# rtc.net
KiCad netlist of a schematic drawn in Altium Designer
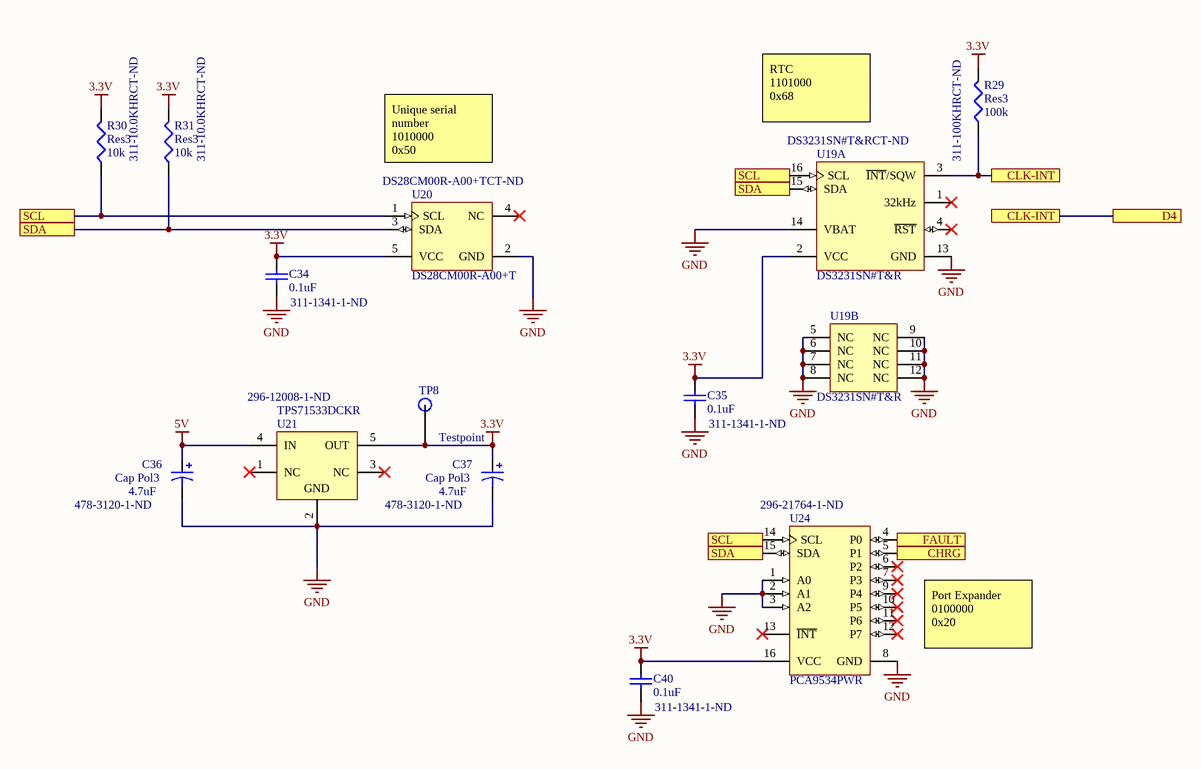
[diagram p0: rtc.SchDoc]

(export (version "E")
  (design (tool "Eeschema 10.0.6"))
  (components
    (comp (ref "C34")
      (value "0.1uF")
      (footprint "1608[0603]")
      (description "Capacitor (Semiconductor SIM Model)")
      (fields
        (field (name "SUPPLIER PART NUMBER 1") "311-1341-1-ND")
        (field (name "MANUFACTURER") "Yageo")
        (field (name "MANUFACTURER PART NUMBER") "CC0603KRX7R8BB104")
      )
      (libsource (lib "Miscellaneous Devices") (part "Cap Semi"))
    )
    (comp (ref "C35")
      (value "0.1uF")
      (footprint "1608[0603]")
      (description "Capacitor (Semiconductor SIM Model)")
      (fields
        (field (name "SUPPLIER PART NUMBER 1") "311-1341-1-ND")
        (field (name "MANUFACTURER") "Yageo")
        (field (name "MANUFACTURER PART NUMBER") "CC0603KRX7R8BB104")
      )
      (libsource (lib "Miscellaneous Devices") (part "Cap Semi"))
    )
    (comp (ref "C36")
      (value "Cap Pol3")
      (footprint "1206-pol")
      (description "Polarized Capacitor (Surface Mount)")
      (fields
        (field (name "ALTIUM_VALUE") "4.7uF")
        (field (name "SUPPLIER PART NUMBER 1") "478-3120-1-ND")
        (field (name "MANUFACTURER") "AVX Corporation")
        (field (name "MANUFACTURER PART NUMBER") "NOJA475M010RWJ")
      )
      (libsource (lib "Miscellaneous Devices") (part "Cap Pol3"))
    )
    (comp (ref "C37")
      (value "Cap Pol3")
      (footprint "1206-pol")
      (description "Polarized Capacitor (Surface Mount)")
      (fields
        (field (name "ALTIUM_VALUE") "4.7uF")
        (field (name "SUPPLIER PART NUMBER 1") "478-3120-1-ND")
        (field (name "MANUFACTURER") "AVX Corporation")
        (field (name "MANUFACTURER PART NUMBER") "NOJA475M010RWJ")
      )
      (libsource (lib "Miscellaneous Devices") (part "Cap Pol3"))
    )
    (comp (ref "C40")
      (value "0.1uF")
      (footprint "1608[0603]")
      (description "Capacitor (Semiconductor SIM Model)")
      (fields
        (field (name "SUPPLIER PART NUMBER 1") "311-1341-1-ND")
        (field (name "MANUFACTURER") "Yageo")
        (field (name "MANUFACTURER PART NUMBER") "CC0603KRX7R8BB104")
      )
      (libsource (lib "Miscellaneous Devices") (part "Cap Semi"))
    )
    (comp (ref "R29")
      (value "Res3")
      (footprint "J1-0603")
      (description "Resistor")
      (fields
        (field (name "ALTIUM_VALUE") "100k")
        (field (name "SUPPLIER PART NUMBER 1") "311-100KHRCT-ND")
        (field (name "MANUFACTURER") "Yageo")
        (field (name "MANUFACTURER PART NUMBER") "RC0603FR-07100KL")
        (field (name "PUBLISHER") "Altium Limited")
      )
      (libsource (lib "Miscellaneous Devices") (part "Res3"))
    )
    (comp (ref "R30")
      (value "Res3")
      (footprint "J1-0603")
      (description "Resistor")
      (fields
        (field (name "ALTIUM_VALUE") "10k")
        (field (name "SUPPLIER PART NUMBER 1") "311-10.0KHRCT-ND")
        (field (name "MANUFACTURER") "Yageo")
        (field (name "MANUFACTURER PART NUMBER") "RC0603FR-0710KL")
        (field (name "PUBLISHER") "Altium Limited")
      )
      (libsource (lib "Miscellaneous Devices") (part "Res3"))
    )
    (comp (ref "R31")
      (value "Res3")
      (footprint "J1-0603")
      (description "Resistor")
      (fields
        (field (name "ALTIUM_VALUE") "10k")
        (field (name "SUPPLIER PART NUMBER 1") "311-10.0KHRCT-ND")
        (field (name "MANUFACTURER") "Yageo")
        (field (name "MANUFACTURER PART NUMBER") "RC0603FR-0710KL")
        (field (name "PUBLISHER") "Altium Limited")
      )
      (libsource (lib "Miscellaneous Devices") (part "Res3"))
    )
    (comp (ref "TP8")
      (value "Testpoint")
      (footprint "testpoint")
      (description "SMT Testpoint")
      (libsource (lib "testpoints") (part "SMT Testpoint"))
    )
    (comp (ref "U19")
      (value "DS3231SN#T&R")
      (footprint "W16#H2_M")
      (fields
        (field (name "SUPPLIER PART NUMBER 1") "DS3231SN#T&RCT-ND")
        (field (name "MANUFACTURER") "Maxim")
      )
      (libsource (lib "Altium Content Vault") (part "MAX-RTC-16-DS3231S-W16#H2"))
    )
    (comp (ref "U20")
      (value "DS28CM00R-A00+T")
      (footprint "U5+1_M")
      (description "I²C/SMBus Silicon Serial Number, 5-pin SOT23, -40° to + 85° C, Pb-Free, Tape and Reel")
      (fields
        (field (name "SUPPLIER PART NUMBER 1") "DS28CM00R-A00+TCT-ND")
        (field (name "MANUFACTURER") "Maxim")
      )
      (libsource (lib "Altium Content Vault") (part "PR-MCTL-DS28CM00-SOT5"))
    )
    (comp (ref "U21")
      (value "TPS71533DCKR")
      (footprint "DCK0005A_L")
      (fields
        (field (name "MANUFACTURER") "Texas Instruments")
        (field (name "SUPPLIER PART NUMBER 1") "296-12008-1-ND")
      )
      (libsource (lib "Altium Content Vault") (part "TI-TPS71XXXX-XXDCK5"))
    )
    (comp (ref "U24")
      (value "PCA9534PWR")
      (footprint "PW0016A_N")
      (fields
        (field (name "MANUFACTURER") "Texas Instruments")
        (field (name "SUPPLIER PART NUMBER 1") "296-21764-1-ND")
      )
      (libsource (lib "Altium Content Vault") (part "TI-PCA9534-TSSOP_PW-16"))
    )
  )
  (nets
    (net (code "1") (name "/CHRG") (class "Default")
      (node (ref "U24") (pin "5") (pinfunction "P1_5") (pintype "bidirectional"))
    )
    (net (code "2") (name "/CLK-INT") (class "Default")
      (node (ref "R29") (pin "1") (pinfunction "1_1") (pintype "passive"))
      (node (ref "U19") (pin "3") (pinfunction "~{INT}/SQW_3") (pintype "open_collector"))
    )
    (net (code "3") (name "/FAULT") (class "Default")
      (node (ref "U24") (pin "4") (pinfunction "P0_4") (pintype "bidirectional"))
    )
    (net (code "4") (name "/SCL") (class "Default")
      (node (ref "R30") (pin "1") (pinfunction "1_1") (pintype "passive"))
      (node (ref "U19") (pin "16") (pinfunction "SCL_16") (pintype "input"))
      (node (ref "U20") (pin "1") (pinfunction "SCL_1") (pintype "input"))
      (node (ref "U24") (pin "14") (pinfunction "SCL_14") (pintype "input"))
    )
    (net (code "5") (name "/SDA") (class "Default")
      (node (ref "R31") (pin "1") (pinfunction "1_1") (pintype "passive"))
      (node (ref "U19") (pin "15") (pinfunction "SDA_15") (pintype "bidirectional"))
      (node (ref "U20") (pin "3") (pinfunction "SDA_3") (pintype "bidirectional"))
      (node (ref "U24") (pin "15") (pinfunction "SDA_15") (pintype "bidirectional"))
    )
    (net (code "6") (name "3.3V") (class "Default")
      (node (ref "C34") (pin "1") (pinfunction "1_1") (pintype "passive"))
      (node (ref "C35") (pin "1") (pinfunction "1_1") (pintype "passive"))
      (node (ref "C37") (pin "1") (pinfunction "1_1") (pintype "passive"))
      (node (ref "C40") (pin "1") (pinfunction "1_1") (pintype "passive"))
      (node (ref "R29") (pin "2") (pinfunction "2_2") (pintype "passive"))
      (node (ref "R30") (pin "2") (pinfunction "2_2") (pintype "passive"))
      (node (ref "R31") (pin "2") (pinfunction "2_2") (pintype "passive"))
      (node (ref "TP8") (pin "1") (pinfunction "1_1") (pintype "passive"))
      (node (ref "U19") (pin "2") (pinfunction "VCC_2") (pintype "power_in"))
      (node (ref "U20") (pin "5") (pinfunction "VCC_5") (pintype "power_in"))
      (node (ref "U21") (pin "5") (pinfunction "OUT_5") (pintype "power_in"))
      (node (ref "U24") (pin "16") (pinfunction "VCC_16") (pintype "power_in"))
    )
    (net (code "7") (name "5V") (class "Default")
      (node (ref "C36") (pin "1") (pinfunction "1_1") (pintype "passive"))
      (node (ref "U21") (pin "4") (pinfunction "IN_4") (pintype "power_in"))
    )
    (net (code "8") (name "GND") (class "Default")
      (node (ref "C34") (pin "2") (pinfunction "2_2") (pintype "passive"))
      (node (ref "C35") (pin "2") (pinfunction "2_2") (pintype "passive"))
      (node (ref "C36") (pin "2") (pinfunction "2_2") (pintype "passive"))
      (node (ref "C37") (pin "2") (pinfunction "2_2") (pintype "passive"))
      (node (ref "C40") (pin "2") (pinfunction "2_2") (pintype "passive"))
      (node (ref "U19") (pin "10") (pinfunction "NC_10") (pintype "passive"))
      (node (ref "U19") (pin "11") (pinfunction "NC_11") (pintype "passive"))
      (node (ref "U19") (pin "12") (pinfunction "NC_12") (pintype "passive"))
      (node (ref "U19") (pin "13") (pinfunction "GND_13") (pintype "power_in"))
      (node (ref "U19") (pin "14") (pinfunction "VBAT_14") (pintype "power_in"))
      (node (ref "U19") (pin "5") (pinfunction "NC_5") (pintype "passive"))
      (node (ref "U19") (pin "6") (pinfunction "NC_6") (pintype "passive"))
      (node (ref "U19") (pin "7") (pinfunction "NC_7") (pintype "passive"))
      (node (ref "U19") (pin "8") (pinfunction "NC_8") (pintype "passive"))
      (node (ref "U19") (pin "9") (pinfunction "NC_9") (pintype "passive"))
      (node (ref "U20") (pin "2") (pinfunction "GND_2") (pintype "power_in"))
      (node (ref "U21") (pin "2") (pinfunction "GND_2") (pintype "power_in"))
      (node (ref "U24") (pin "1") (pinfunction "A0_1") (pintype "input"))
      (node (ref "U24") (pin "2") (pinfunction "A1_2") (pintype "input"))
      (node (ref "U24") (pin "3") (pinfunction "A2_3") (pintype "input"))
      (node (ref "U24") (pin "8") (pinfunction "GND_8") (pintype "power_in"))
    )
    (net (code "9") (name "unconnected-(U19A-32kHz-Pad1)") (class "Default")
      (node (ref "U19") (pin "1") (pinfunction "32kHz_1") (pintype "open_collector+no_connect"))
    )
    (net (code "10") (name "unconnected-(U19A-~{RST}-Pad4)") (class "Default")
      (node (ref "U19") (pin "4") (pinfunction "~{RST}_4") (pintype "bidirectional+no_connect"))
    )
    (net (code "11") (name "unconnected-(U20-NC-Pad4)") (class "Default")
      (node (ref "U20") (pin "4") (pinfunction "NC_4") (pintype "passive+no_connect"))
    )
    (net (code "12") (name "unconnected-(U21-NC-Pad1)") (class "Default")
      (node (ref "U21") (pin "1") (pinfunction "NC_1") (pintype "passive+no_connect"))
    )
    (net (code "13") (name "unconnected-(U21-NC-Pad3)") (class "Default")
      (node (ref "U21") (pin "3") (pinfunction "NC_3") (pintype "passive+no_connect"))
    )
    (net (code "14") (name "unconnected-(U24-P2-Pad6)") (class "Default")
      (node (ref "U24") (pin "6") (pinfunction "P2_6") (pintype "bidirectional+no_connect"))
    )
    (net (code "15") (name "unconnected-(U24-P3-Pad7)") (class "Default")
      (node (ref "U24") (pin "7") (pinfunction "P3_7") (pintype "bidirectional+no_connect"))
    )
    (net (code "16") (name "unconnected-(U24-P4-Pad9)") (class "Default")
      (node (ref "U24") (pin "9") (pinfunction "P4_9") (pintype "bidirectional+no_connect"))
    )
    (net (code "17") (name "unconnected-(U24-P5-Pad10)") (class "Default")
      (node (ref "U24") (pin "10") (pinfunction "P5_10") (pintype "bidirectional+no_connect"))
    )
    (net (code "18") (name "unconnected-(U24-P6-Pad11)") (class "Default")
      (node (ref "U24") (pin "11") (pinfunction "P6_11") (pintype "bidirectional+no_connect"))
    )
    (net (code "19") (name "unconnected-(U24-P7-Pad12)") (class "Default")
      (node (ref "U24") (pin "12") (pinfunction "P7_12") (pintype "bidirectional+no_connect"))
    )
    (net (code "20") (name "unconnected-(U24-~{INT}-Pad13)") (class "Default")
      (node (ref "U24") (pin "13") (pinfunction "~{INT}_13") (pintype "open_collector+no_connect"))
    )
  )
)
